# padometer.net
KiCad netlist of a schematic drawn in Altium Designer
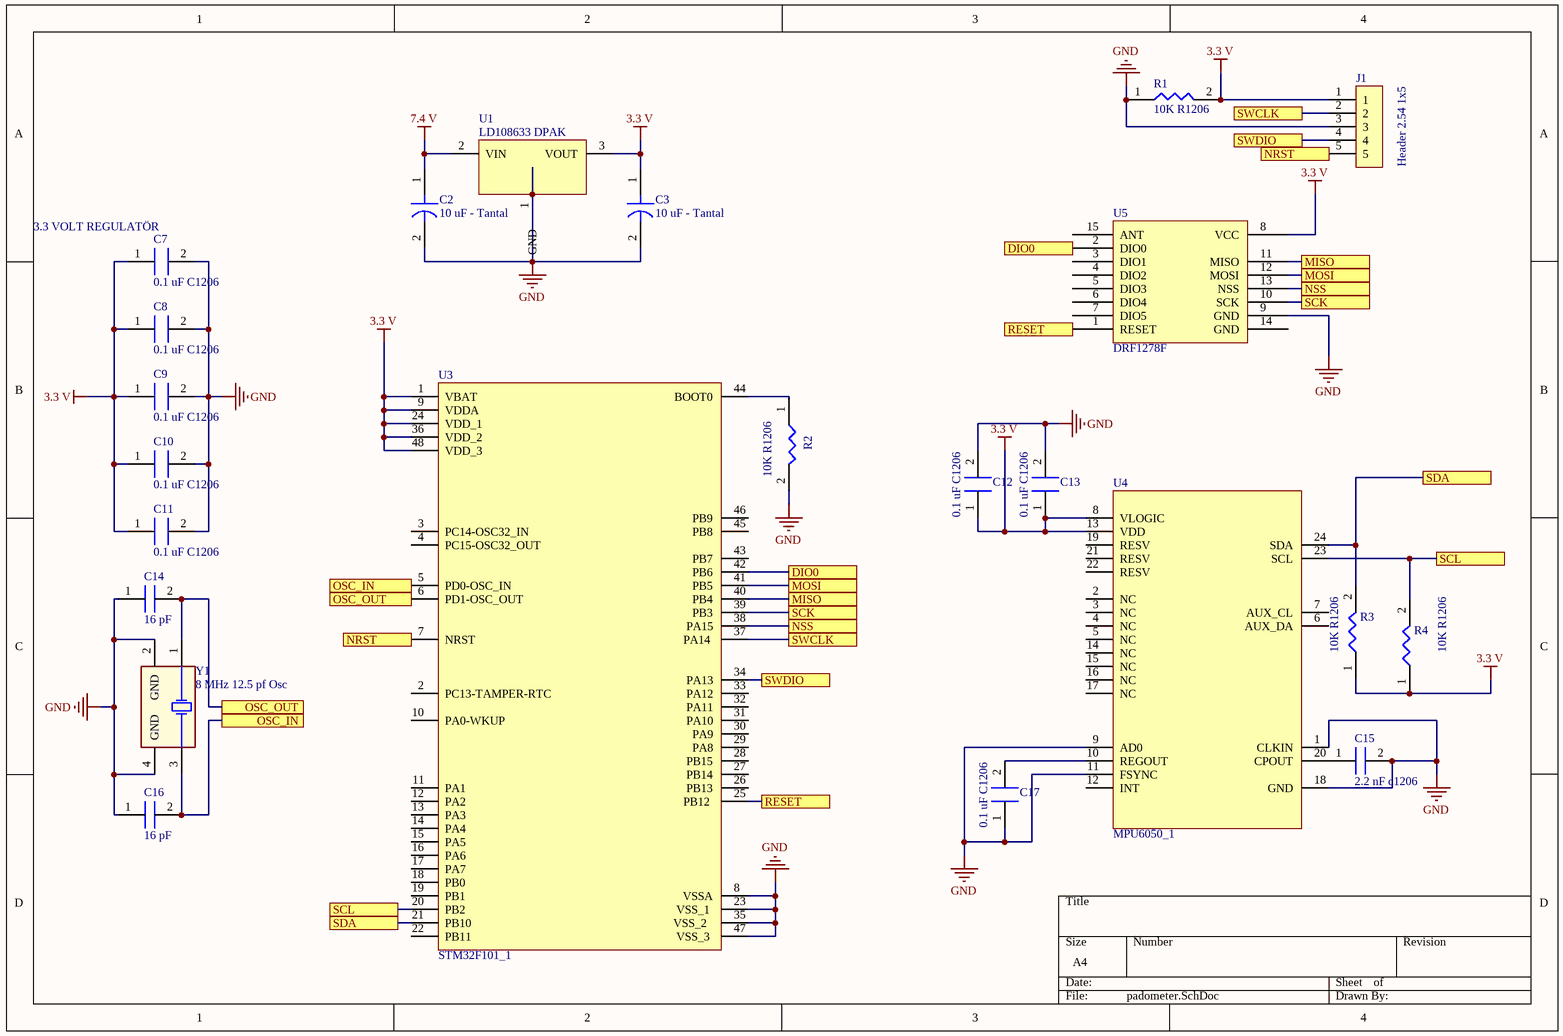
[diagram p0: padometer.SchDoc]

(export (version "E")
  (design (tool "Eeschema 10.0.6"))
  (components
    (comp (ref "C2")
      (value "10 uF - Tantal")
      (footprint "C1206- TANTAL")
      (libsource (lib "SchlibPadometer") (part "10 uF - Tantal"))
    )
    (comp (ref "C3")
      (value "10 uF - Tantal")
      (footprint "C1206- TANTAL")
      (libsource (lib "SchlibPadometer") (part "10 uF - Tantal"))
    )
    (comp (ref "C7")
      (value "0.1 uF C1206")
      (footprint "C1206")
      (libsource (lib "SchlibPadometer") (part "0.1 uF C1206"))
    )
    (comp (ref "C8")
      (value "0.1 uF C1206")
      (footprint "C1206")
      (libsource (lib "SchlibPadometer") (part "0.1 uF C1206"))
    )
    (comp (ref "C9")
      (value "0.1 uF C1206")
      (footprint "C1206")
      (libsource (lib "SchlibPadometer") (part "0.1 uF C1206"))
    )
    (comp (ref "C10")
      (value "0.1 uF C1206")
      (footprint "C1206")
      (libsource (lib "SchlibPadometer") (part "0.1 uF C1206"))
    )
    (comp (ref "C11")
      (value "0.1 uF C1206")
      (footprint "C1206")
      (libsource (lib "SchlibPadometer") (part "0.1 uF C1206"))
    )
    (comp (ref "C12")
      (value "0.1 uF C1206")
      (footprint "C1206")
      (libsource (lib "SchlibPadometer") (part "0.1 uF C1206"))
    )
    (comp (ref "C13")
      (value "0.1 uF C1206")
      (footprint "C1206")
      (libsource (lib "SchlibPadometer") (part "0.1 uF C1206"))
    )
    (comp (ref "C14") (value "16 pF") (footprint "C1206") (libsource (lib "SchlibPadometer") (part "16 pF")))
    (comp (ref "C15")
      (value "2.2 nF c1206")
      (footprint "C1206")
      (libsource (lib "SchlibPadometer") (part "2.2 nF c1206"))
    )
    (comp (ref "C16") (value "16 pF") (footprint "C1206") (libsource (lib "SchlibPadometer") (part "16 pF")))
    (comp (ref "C17")
      (value "0.1 uF C1206")
      (footprint "C1206")
      (libsource (lib "SchlibPadometer") (part "0.1 uF C1206"))
    )
    (comp (ref "J1")
      (value "Header 2.54 1x5")
      (footprint "Header 2.54 1x5")
      (libsource (lib "SchlibPadometer") (part "Header 2.54 1x5"))
    )
    (comp (ref "R1")
      (value "10K R1206")
      (footprint "R1206 Resıstor")
      (libsource (lib "SchlibPadometer") (part "10K R1206"))
    )
    (comp (ref "R2")
      (value "10K R1206")
      (footprint "R1206 Resıstor")
      (libsource (lib "SchlibPadometer") (part "10K R1206"))
    )
    (comp (ref "R3")
      (value "10K R1206")
      (footprint "R1206 Resıstor")
      (libsource (lib "SchlibPadometer") (part "10K R1206"))
    )
    (comp (ref "R4")
      (value "10K R1206")
      (footprint "R1206 Resıstor")
      (libsource (lib "SchlibPadometer") (part "10K R1206"))
    )
    (comp (ref "U1")
      (value "LD108633 DPAK")
      (footprint "DPAK228P972X230-3N")
      (description "LD1086 3.3V REGULATOR")
      (libsource (lib "SchlibPadometer") (part "LD108633 DPAK"))
    )
    (comp (ref "U3")
      (value "STM32F101_1")
      (footprint "LQFP48-STM")
      (description "STM32F101 48 PİNLİ MİKROİŞLEMCİ")
      (libsource (lib "SchlibPadometer") (part "STM32F101_1"))
    )
    (comp (ref "U4")
      (value "MPU6050_1")
      (footprint "QFN50P400X400X90_HS-25N")
      (description "MPU6050 GYRO")
      (libsource (lib "SchlibPadometer") (part "MPU6050_1"))
    )
    (comp (ref "U5")
      (value "DRF1278F")
      (footprint "DRF1278F")
      (libsource (lib "SchlibPadometer") (part "DRF1278F"))
    )
    (comp (ref "Y1")
      (value "8 MHz 12.5 pf Osc")
      (footprint "8 MHZ Osc.")
      (libsource (lib "SchlibPadometer") (part "8 MHz 12.5 pf Osc"))
    )
  )
  (nets
    (net (code "1") (name "/DIO0") (class "Default")
      (node (ref "U3") (pin "42") (pinfunction "PB6_42") (pintype "passive"))
      (node (ref "U5") (pin "2") (pinfunction "DIO0_2") (pintype "passive"))
    )
    (net (code "2") (name "/MISO") (class "Default")
      (node (ref "U3") (pin "40") (pinfunction "PB4_40") (pintype "passive"))
      (node (ref "U5") (pin "11") (pinfunction "MISO_11") (pintype "passive"))
    )
    (net (code "3") (name "/MOSI") (class "Default")
      (node (ref "U3") (pin "41") (pinfunction "PB5_41") (pintype "passive"))
      (node (ref "U5") (pin "12") (pinfunction "MOSI_12") (pintype "passive"))
    )
    (net (code "4") (name "/NRST") (class "Default")
      (node (ref "J1") (pin "5") (pinfunction "5_5") (pintype "passive"))
      (node (ref "U3") (pin "7") (pinfunction "NRST_7") (pintype "passive"))
    )
    (net (code "5") (name "/NSS") (class "Default")
      (node (ref "U3") (pin "38") (pinfunction "PA15_38") (pintype "passive"))
      (node (ref "U5") (pin "13") (pinfunction "NSS_13") (pintype "passive"))
    )
    (net (code "6") (name "/OSC_IN") (class "Default")
      (node (ref "C16") (pin "2") (pinfunction "2_2") (pintype "passive"))
      (node (ref "U3") (pin "5") (pinfunction "PD0-OSC_IN_5") (pintype "passive"))
      (node (ref "Y1") (pin "3") (pintype "passive"))
    )
    (net (code "7") (name "/OSC_OUT") (class "Default")
      (node (ref "C14") (pin "2") (pinfunction "2_2") (pintype "passive"))
      (node (ref "U3") (pin "6") (pinfunction "PD1-OSC_OUT_6") (pintype "passive"))
      (node (ref "Y1") (pin "1") (pintype "power_in"))
    )
    (net (code "8") (name "/RESET") (class "Default")
      (node (ref "U3") (pin "25") (pinfunction "PB12_25") (pintype "passive"))
      (node (ref "U5") (pin "1") (pinfunction "RESET_1") (pintype "passive"))
    )
    (net (code "9") (name "/SCK") (class "Default")
      (node (ref "U3") (pin "39") (pinfunction "PB3_39") (pintype "passive"))
      (node (ref "U5") (pin "10") (pinfunction "SCK_10") (pintype "passive"))
    )
    (net (code "10") (name "/SCL") (class "Default")
      (node (ref "R4") (pin "2") (pinfunction "2_2") (pintype "passive"))
      (node (ref "U3") (pin "20") (pinfunction "PB2_20") (pintype "passive"))
      (node (ref "U4") (pin "23") (pinfunction "SCL_23") (pintype "passive"))
    )
    (net (code "11") (name "/SDA") (class "Default")
      (node (ref "R3") (pin "2") (pinfunction "2_2") (pintype "passive"))
      (node (ref "U3") (pin "21") (pinfunction "PB10_21") (pintype "passive"))
      (node (ref "U4") (pin "24") (pinfunction "SDA_24") (pintype "passive"))
    )
    (net (code "12") (name "/SWCLK") (class "Default")
      (node (ref "J1") (pin "2") (pinfunction "2_2") (pintype "passive"))
      (node (ref "U3") (pin "37") (pinfunction "PA14_37") (pintype "passive"))
    )
    (net (code "13") (name "/SWDIO") (class "Default")
      (node (ref "J1") (pin "4") (pinfunction "4_4") (pintype "passive"))
      (node (ref "U3") (pin "34") (pinfunction "PA13_34") (pintype "passive"))
    )
    (net (code "14") (name "3.3 V") (class "Default")
      (node (ref "C10") (pin "1") (pinfunction "1_1") (pintype "passive"))
      (node (ref "C11") (pin "1") (pinfunction "1_1") (pintype "passive"))
      (node (ref "C12") (pin "1") (pinfunction "1_1") (pintype "passive"))
      (node (ref "C13") (pin "1") (pinfunction "1_1") (pintype "passive"))
      (node (ref "C3") (pin "1") (pinfunction "1_1") (pintype "passive"))
      (node (ref "C7") (pin "1") (pinfunction "1_1") (pintype "passive"))
      (node (ref "C8") (pin "1") (pinfunction "1_1") (pintype "passive"))
      (node (ref "C9") (pin "1") (pinfunction "1_1") (pintype "passive"))
      (node (ref "J1") (pin "1") (pinfunction "1_1") (pintype "passive"))
      (node (ref "R1") (pin "2") (pinfunction "2_2") (pintype "passive"))
      (node (ref "R3") (pin "1") (pinfunction "1_1") (pintype "passive"))
      (node (ref "R4") (pin "1") (pinfunction "1_1") (pintype "passive"))
      (node (ref "U1") (pin "3") (pinfunction "VOUT_3") (pintype "passive"))
      (node (ref "U3") (pin "1") (pinfunction "VBAT_1") (pintype "passive"))
      (node (ref "U3") (pin "24") (pinfunction "VDD_1_24") (pintype "passive"))
      (node (ref "U3") (pin "36") (pinfunction "VDD_2_36") (pintype "passive"))
      (node (ref "U3") (pin "48") (pinfunction "VDD_3_48") (pintype "passive"))
      (node (ref "U3") (pin "9") (pinfunction "VDDA_9") (pintype "passive"))
      (node (ref "U4") (pin "13") (pinfunction "VDD_13") (pintype "passive"))
      (node (ref "U4") (pin "8") (pinfunction "VLOGIC_8") (pintype "passive"))
      (node (ref "U5") (pin "8") (pinfunction "VCC_8") (pintype "passive"))
    )
    (net (code "15") (name "7.4 V") (class "Default")
      (node (ref "C2") (pin "1") (pinfunction "1_1") (pintype "passive"))
      (node (ref "U1") (pin "2") (pinfunction "VIN_2") (pintype "passive"))
    )
    (net (code "16") (name "GND") (class "Default")
      (node (ref "C10") (pin "2") (pinfunction "2_2") (pintype "passive"))
      (node (ref "C11") (pin "2") (pinfunction "2_2") (pintype "passive"))
      (node (ref "C12") (pin "2") (pinfunction "2_2") (pintype "passive"))
      (node (ref "C13") (pin "2") (pinfunction "2_2") (pintype "passive"))
      (node (ref "C14") (pin "1") (pinfunction "1_1") (pintype "passive"))
      (node (ref "C15") (pin "2") (pinfunction "2_2") (pintype "passive"))
      (node (ref "C16") (pin "1") (pinfunction "1_1") (pintype "passive"))
      (node (ref "C17") (pin "1") (pinfunction "1_1") (pintype "passive"))
      (node (ref "C2") (pin "2") (pinfunction "2_2") (pintype "passive"))
      (node (ref "C3") (pin "2") (pinfunction "2_2") (pintype "passive"))
      (node (ref "C7") (pin "2") (pinfunction "2_2") (pintype "passive"))
      (node (ref "C8") (pin "2") (pinfunction "2_2") (pintype "passive"))
      (node (ref "C9") (pin "2") (pinfunction "2_2") (pintype "passive"))
      (node (ref "J1") (pin "3") (pinfunction "3_3") (pintype "passive"))
      (node (ref "R1") (pin "1") (pinfunction "1_1") (pintype "passive"))
      (node (ref "R2") (pin "2") (pinfunction "2_2") (pintype "passive"))
      (node (ref "U1") (pin "1") (pinfunction "GND_1") (pintype "passive"))
      (node (ref "U3") (pin "23") (pinfunction "VSS_1_23") (pintype "passive"))
      (node (ref "U3") (pin "35") (pinfunction "VSS_2_35") (pintype "passive"))
      (node (ref "U3") (pin "47") (pinfunction "VSS_3_47") (pintype "passive"))
      (node (ref "U3") (pin "8") (pinfunction "VSSA_8") (pintype "passive"))
      (node (ref "U4") (pin "1") (pinfunction "CLKIN_1") (pintype "passive"))
      (node (ref "U4") (pin "11") (pinfunction "FSYNC_11") (pintype "passive"))
      (node (ref "U4") (pin "18") (pinfunction "GND_18") (pintype "passive"))
      (node (ref "U4") (pin "9") (pinfunction "AD0_9") (pintype "passive"))
      (node (ref "U5") (pin "9") (pinfunction "GND_9") (pintype "passive"))
      (node (ref "Y1") (pin "2") (pinfunction "GND_2") (pintype "power_in"))
      (node (ref "Y1") (pin "4") (pinfunction "GND_4") (pintype "passive"))
    )
    (net (code "17") (name "Net-(U3-BOOT0)") (class "Default")
      (node (ref "R2") (pin "1") (pinfunction "1_1") (pintype "passive"))
      (node (ref "U3") (pin "44") (pinfunction "BOOT0_44") (pintype "passive"))
    )
    (net (code "18") (name "Net-(U4-CPOUT)") (class "Default")
      (node (ref "C15") (pin "1") (pinfunction "1_1") (pintype "passive"))
      (node (ref "U4") (pin "20") (pinfunction "CPOUT_20") (pintype "passive"))
    )
    (net (code "19") (name "Net-(U4-REGOUT)") (class "Default")
      (node (ref "C17") (pin "2") (pinfunction "2_2") (pintype "passive"))
      (node (ref "U4") (pin "10") (pinfunction "REGOUT_10") (pintype "passive"))
    )
    (net (code "20") (name "unconnected-(U3-PA0-WKUP-Pad10)") (class "Default")
      (node (ref "U3") (pin "10") (pinfunction "PA0-WKUP_10") (pintype "passive"))
    )
    (net (code "21") (name "unconnected-(U3-PA1-Pad11)") (class "Default")
      (node (ref "U3") (pin "11") (pinfunction "PA1_11") (pintype "passive"))
    )
    (net (code "22") (name "unconnected-(U3-PA2-Pad12)") (class "Default")
      (node (ref "U3") (pin "12") (pinfunction "PA2_12") (pintype "passive"))
    )
    (net (code "23") (name "unconnected-(U3-PA3-Pad13)") (class "Default")
      (node (ref "U3") (pin "13") (pinfunction "PA3_13") (pintype "passive"))
    )
    (net (code "24") (name "unconnected-(U3-PA4-Pad14)") (class "Default")
      (node (ref "U3") (pin "14") (pinfunction "PA4_14") (pintype "passive"))
    )
    (net (code "25") (name "unconnected-(U3-PA5-Pad15)") (class "Default")
      (node (ref "U3") (pin "15") (pinfunction "PA5_15") (pintype "passive"))
    )
    (net (code "26") (name "unconnected-(U3-PA6-Pad16)") (class "Default")
      (node (ref "U3") (pin "16") (pinfunction "PA6_16") (pintype "passive"))
    )
    (net (code "27") (name "unconnected-(U3-PA7-Pad17)") (class "Default")
      (node (ref "U3") (pin "17") (pinfunction "PA7_17") (pintype "passive"))
    )
    (net (code "28") (name "unconnected-(U3-PA8-Pad29)") (class "Default")
      (node (ref "U3") (pin "29") (pinfunction "PA8_29") (pintype "passive"))
    )
    (net (code "29") (name "unconnected-(U3-PA9-Pad30)") (class "Default")
      (node (ref "U3") (pin "30") (pinfunction "PA9_30") (pintype "passive"))
    )
    (net (code "30") (name "unconnected-(U3-PA10-Pad31)") (class "Default")
      (node (ref "U3") (pin "31") (pinfunction "PA10_31") (pintype "passive"))
    )
    (net (code "31") (name "unconnected-(U3-PA11-Pad32)") (class "Default")
      (node (ref "U3") (pin "32") (pinfunction "PA11_32") (pintype "passive"))
    )
    (net (code "32") (name "unconnected-(U3-PA12-Pad33)") (class "Default")
      (node (ref "U3") (pin "33") (pinfunction "PA12_33") (pintype "passive"))
    )
    (net (code "33") (name "unconnected-(U3-PB0-Pad18)") (class "Default")
      (node (ref "U3") (pin "18") (pinfunction "PB0_18") (pintype "passive"))
    )
    (net (code "34") (name "unconnected-(U3-PB1-Pad19)") (class "Default")
      (node (ref "U3") (pin "19") (pinfunction "PB1_19") (pintype "passive"))
    )
    (net (code "35") (name "unconnected-(U3-PB7-Pad43)") (class "Default")
      (node (ref "U3") (pin "43") (pinfunction "PB7_43") (pintype "passive"))
    )
    (net (code "36") (name "unconnected-(U3-PB8-Pad45)") (class "Default")
      (node (ref "U3") (pin "45") (pinfunction "PB8_45") (pintype "passive"))
    )
    (net (code "37") (name "unconnected-(U3-PB9-Pad46)") (class "Default")
      (node (ref "U3") (pin "46") (pinfunction "PB9_46") (pintype "passive"))
    )
    (net (code "38") (name "unconnected-(U3-PB11-Pad22)") (class "Default")
      (node (ref "U3") (pin "22") (pinfunction "PB11_22") (pintype "passive"))
    )
    (net (code "39") (name "unconnected-(U3-PB13-Pad26)") (class "Default")
      (node (ref "U3") (pin "26") (pinfunction "PB13_26") (pintype "passive"))
    )
    (net (code "40") (name "unconnected-(U3-PB14-Pad27)") (class "Default")
      (node (ref "U3") (pin "27") (pinfunction "PB14_27") (pintype "passive"))
    )
    (net (code "41") (name "unconnected-(U3-PB15-Pad28)") (class "Default")
      (node (ref "U3") (pin "28") (pinfunction "PB15_28") (pintype "passive"))
    )
    (net (code "42") (name "unconnected-(U3-PC13-TAMPER-RTC-Pad2)") (class "Default")
      (node (ref "U3") (pin "2") (pinfunction "PC13-TAMPER-RTC_2") (pintype "passive"))
    )
    (net (code "43") (name "unconnected-(U3-PC14-OSC32_IN-Pad3)") (class "Default")
      (node (ref "U3") (pin "3") (pinfunction "PC14-OSC32_IN_3") (pintype "passive"))
    )
    (net (code "44") (name "unconnected-(U3-PC15-OSC32_OUT-Pad4)") (class "Default")
      (node (ref "U3") (pin "4") (pinfunction "PC15-OSC32_OUT_4") (pintype "passive"))
    )
    (net (code "45") (name "unconnected-(U4-AUX_CL-Pad7)") (class "Default")
      (node (ref "U4") (pin "7") (pinfunction "AUX_CL_7") (pintype "passive"))
    )
    (net (code "46") (name "unconnected-(U4-AUX_DA-Pad6)") (class "Default")
      (node (ref "U4") (pin "6") (pinfunction "AUX_DA_6") (pintype "passive"))
    )
    (net (code "47") (name "unconnected-(U4-INT-Pad12)") (class "Default")
      (node (ref "U4") (pin "12") (pinfunction "INT_12") (pintype "passive"))
    )
    (net (code "48") (name "unconnected-(U4-NC-Pad2)") (class "Default")
      (node (ref "U4") (pin "2") (pinfunction "NC_2") (pintype "passive"))
    )
    (net (code "49") (name "unconnected-(U4-NC-Pad3)") (class "Default")
      (node (ref "U4") (pin "3") (pinfunction "NC_3") (pintype "passive"))
    )
    (net (code "50") (name "unconnected-(U4-NC-Pad4)") (class "Default")
      (node (ref "U4") (pin "4") (pinfunction "NC_4") (pintype "passive"))
    )
    (net (code "51") (name "unconnected-(U4-NC-Pad5)") (class "Default")
      (node (ref "U4") (pin "5") (pinfunction "NC_5") (pintype "passive"))
    )
    (net (code "52") (name "unconnected-(U4-NC-Pad14)") (class "Default")
      (node (ref "U4") (pin "14") (pinfunction "NC_14") (pintype "passive"))
    )
    (net (code "53") (name "unconnected-(U4-NC-Pad15)") (class "Default")
      (node (ref "U4") (pin "15") (pinfunction "NC_15") (pintype "passive"))
    )
    (net (code "54") (name "unconnected-(U4-NC-Pad16)") (class "Default")
      (node (ref "U4") (pin "16") (pinfunction "NC_16") (pintype "passive"))
    )
    (net (code "55") (name "unconnected-(U4-NC-Pad17)") (class "Default")
      (node (ref "U4") (pin "17") (pinfunction "NC_17") (pintype "passive"))
    )
    (net (code "56") (name "unconnected-(U4-RESV-Pad19)") (class "Default")
      (node (ref "U4") (pin "19") (pinfunction "RESV_19") (pintype "passive"))
    )
    (net (code "57") (name "unconnected-(U4-RESV-Pad21)") (class "Default")
      (node (ref "U4") (pin "21") (pinfunction "RESV_21") (pintype "passive"))
    )
    (net (code "58") (name "unconnected-(U4-RESV-Pad22)") (class "Default")
      (node (ref "U4") (pin "22") (pinfunction "RESV_22") (pintype "passive"))
    )
    (net (code "59") (name "unconnected-(U5-ANT-Pad15)") (class "Default")
      (node (ref "U5") (pin "15") (pinfunction "ANT_15") (pintype "passive"))
    )
    (net (code "60") (name "unconnected-(U5-DIO1-Pad3)") (class "Default")
      (node (ref "U5") (pin "3") (pinfunction "DIO1_3") (pintype "passive"))
    )
    (net (code "61") (name "unconnected-(U5-DIO2-Pad4)") (class "Default")
      (node (ref "U5") (pin "4") (pinfunction "DIO2_4") (pintype "passive"))
    )
    (net (code "62") (name "unconnected-(U5-DIO3-Pad5)") (class "Default")
      (node (ref "U5") (pin "5") (pinfunction "DIO3_5") (pintype "passive"))
    )
    (net (code "63") (name "unconnected-(U5-DIO4-Pad6)") (class "Default")
      (node (ref "U5") (pin "6") (pinfunction "DIO4_6") (pintype "passive"))
    )
    (net (code "64") (name "unconnected-(U5-DIO5-Pad7)") (class "Default")
      (node (ref "U5") (pin "7") (pinfunction "DIO5_7") (pintype "passive"))
    )
    (net (code "65") (name "unconnected-(U5-GND-Pad14)") (class "Default")
      (node (ref "U5") (pin "14") (pinfunction "GND_14") (pintype "passive"))
    )
  )
)
